# Receptor_Solo.net
KiCad netlist of a schematic drawn in EAGLE
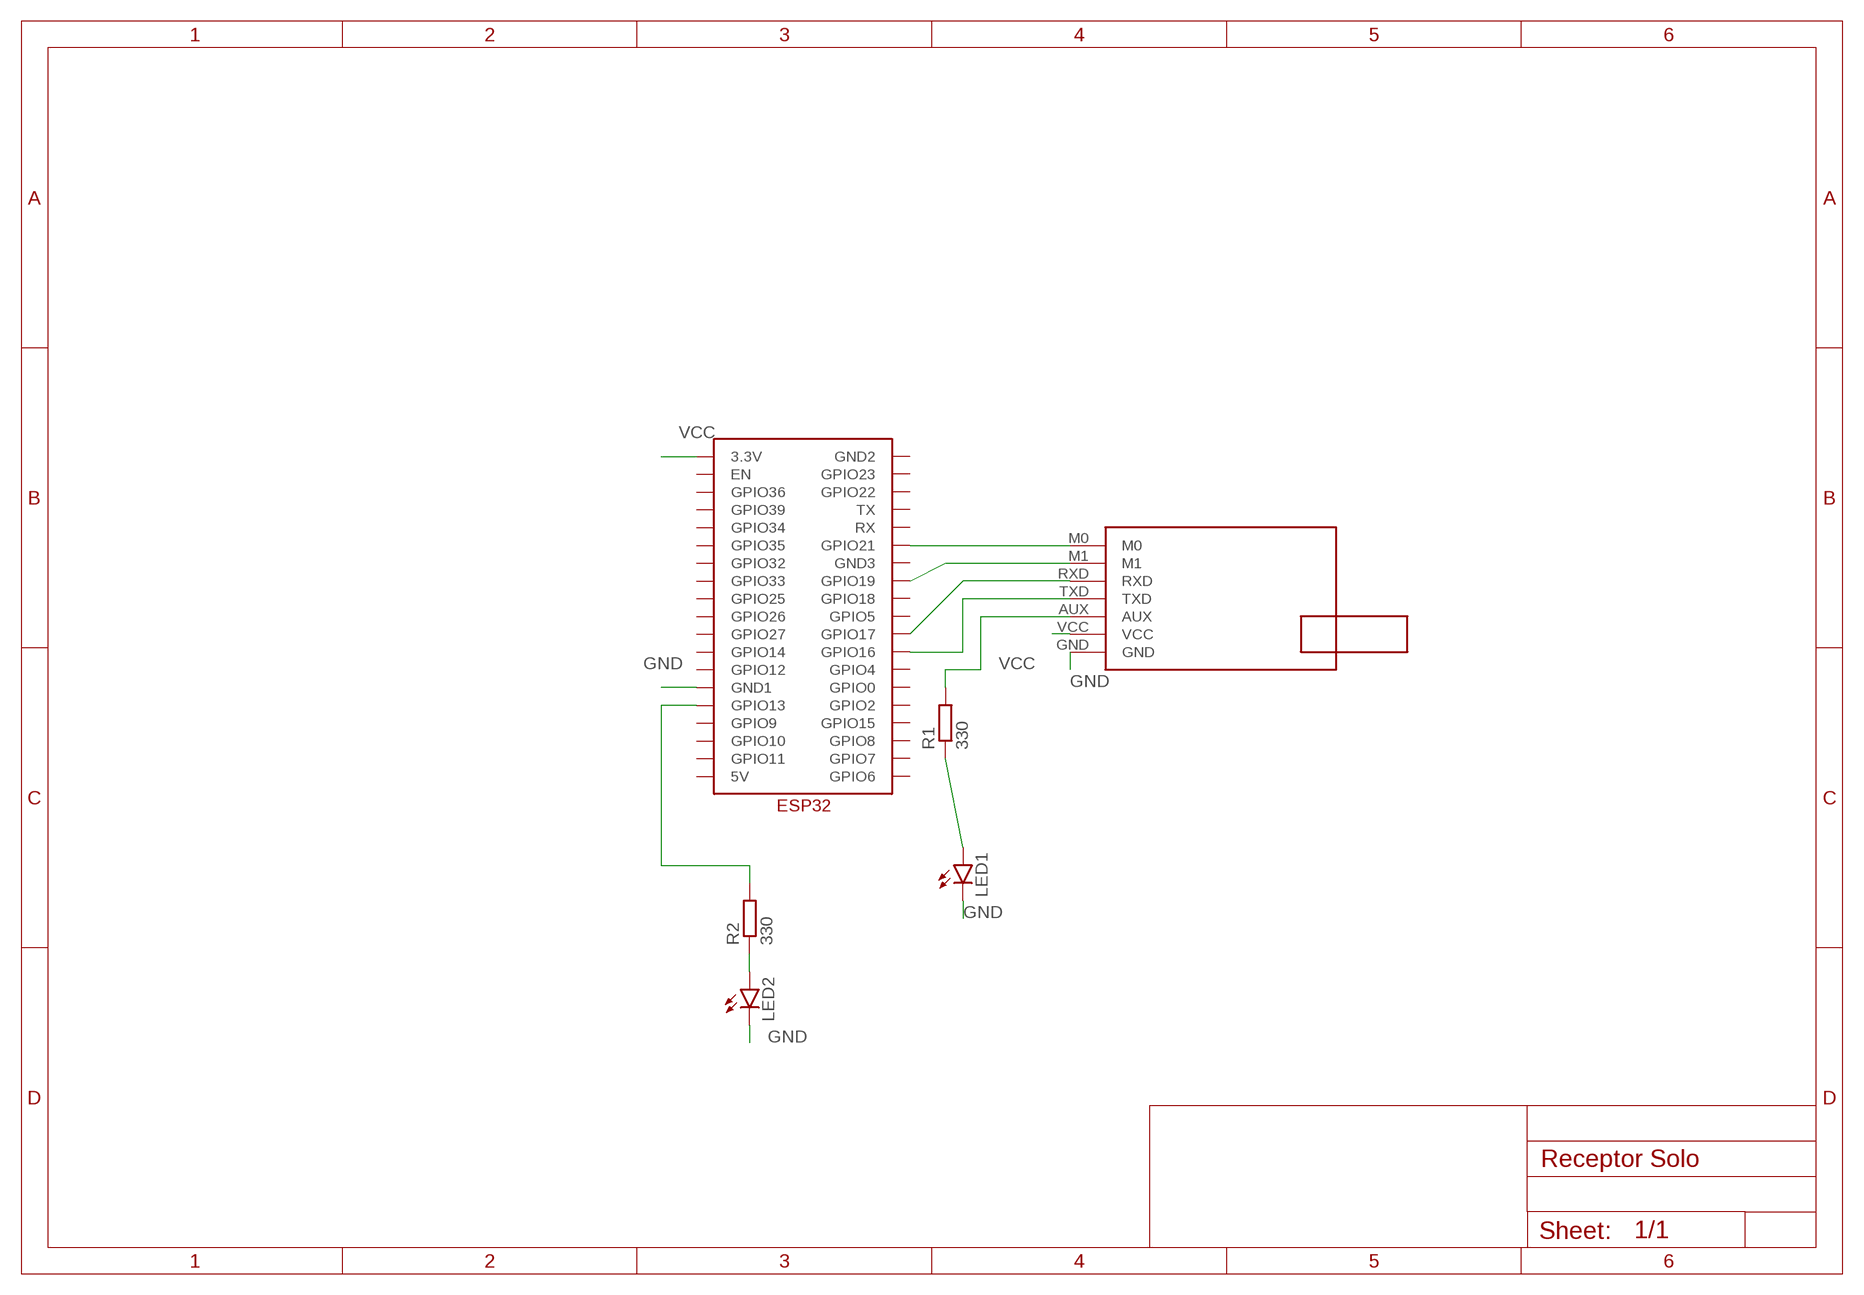
[diagram p0: schematic, sheet 1]

(export (version "E")
  (design (tool "Eeschema 10.0.6"))
  (components
    (comp (ref "LED1")
      (value "LED5MM")
      (footprint "eagle-import:LED5MM")
      (libsource (lib "eagle-import") (part "LED5MM"))
    )
    (comp (ref "LED2")
      (value "LED5MM")
      (footprint "eagle-import:LED5MM")
      (libsource (lib "eagle-import") (part "LED5MM"))
    )
    (comp (ref "R1")
      (value "330")
      (footprint "eagle-import:0207_10")
      (libsource (lib "eagle-import") (part "R-EU_0207/10"))
    )
    (comp (ref "R2")
      (value "330")
      (footprint "eagle-import:0207_10")
      (libsource (lib "eagle-import") (part "R-EU_0207/10"))
    )
    (comp (ref "U$1")
      (value "ESP32")
      (footprint "eagle-import:ESP32")
      (libsource (lib "eagle-import") (part "ESP32"))
    )
    (comp (ref "U$2")
      (value "E22-400T30D")
      (footprint "eagle-import:E22-400T30D_FOOTPRINT")
      (libsource (lib "eagle-import") (part "E22-400T30D"))
    )
  )
  (nets
    (net (code "1") (name "/GND") (class "Default")
      (node (ref "LED1") (pin "K") (pinfunction "C_K") (pintype "passive"))
      (node (ref "LED2") (pin "K") (pinfunction "C_K") (pintype "passive"))
      (node (ref "U$1") (pin "GND1") (pinfunction "GND1_GND1") (pintype "bidirectional"))
      (node (ref "U$2") (pin "GND") (pinfunction "GND_GND") (pintype "bidirectional"))
    )
    (net (code "2") (name "/VCC") (class "Default")
      (node (ref "U$1") (pin "3.3V") (pinfunction "3.3V_3.3V") (pintype "bidirectional"))
      (node (ref "U$2") (pin "VCC") (pinfunction "VCC_VCC") (pintype "bidirectional"))
    )
    (net (code "3") (name "Net-(LED1-PadA)") (class "Default")
      (node (ref "LED1") (pin "A") (pinfunction "A_A") (pintype "passive"))
      (node (ref "R1") (pin "1") (pinfunction "1_1") (pintype "passive"))
    )
    (net (code "4") (name "Net-(LED2-PadA)") (class "Default")
      (node (ref "LED2") (pin "A") (pinfunction "A_A") (pintype "passive"))
      (node (ref "R2") (pin "1") (pinfunction "1_1") (pintype "passive"))
    )
    (net (code "5") (name "Net-(R1-Pad2)") (class "Default")
      (node (ref "R1") (pin "2") (pinfunction "2_2") (pintype "passive"))
      (node (ref "U$2") (pin "AUX") (pinfunction "AUX_AUX") (pintype "bidirectional"))
    )
    (net (code "6") (name "Net-(R2-Pad2)") (class "Default")
      (node (ref "R2") (pin "2") (pinfunction "2_2") (pintype "passive"))
      (node (ref "U$1") (pin "GPIO13") (pinfunction "GPIO13_GPIO13") (pintype "bidirectional"))
    )
    (net (code "7") (name "Net-(U$1-PadGPIO16)") (class "Default")
      (node (ref "U$1") (pin "GPIO16") (pinfunction "GPIO16_GPIO16") (pintype "bidirectional"))
      (node (ref "U$2") (pin "TXD") (pinfunction "TXD_TXD") (pintype "bidirectional"))
    )
    (net (code "8") (name "Net-(U$1-PadGPIO17)") (class "Default")
      (node (ref "U$1") (pin "GPIO17") (pinfunction "GPIO17_GPIO17") (pintype "bidirectional"))
      (node (ref "U$2") (pin "RXD") (pinfunction "RXD_RXD") (pintype "bidirectional"))
    )
    (net (code "9") (name "Net-(U$1-PadGPIO19)") (class "Default")
      (node (ref "U$1") (pin "GPIO19") (pinfunction "GPIO19_GPIO19") (pintype "bidirectional"))
      (node (ref "U$2") (pin "M1") (pinfunction "M1_M1") (pintype "bidirectional"))
    )
    (net (code "10") (name "Net-(U$1-PadGPIO21)") (class "Default")
      (node (ref "U$1") (pin "GPIO21") (pinfunction "GPIO21_GPIO21") (pintype "bidirectional"))
      (node (ref "U$2") (pin "M0") (pinfunction "M0_M0") (pintype "bidirectional"))
    )
    (net (code "11") (name "unconnected-(U$1-Pad5V)") (class "Default")
      (node (ref "U$1") (pin "5V") (pinfunction "5V_5V") (pintype "bidirectional"))
    )
    (net (code "12") (name "unconnected-(U$1-PadEN)") (class "Default")
      (node (ref "U$1") (pin "EN") (pinfunction "EN_EN") (pintype "bidirectional"))
    )
    (net (code "13") (name "unconnected-(U$1-PadGND2)") (class "Default")
      (node (ref "U$1") (pin "GND2") (pinfunction "GND2_GND2") (pintype "bidirectional"))
    )
    (net (code "14") (name "unconnected-(U$1-PadGND3)") (class "Default")
      (node (ref "U$1") (pin "GND3") (pinfunction "GND3_GND3") (pintype "bidirectional"))
    )
    (net (code "15") (name "unconnected-(U$1-PadGPIO0)") (class "Default")
      (node (ref "U$1") (pin "GPIO0") (pinfunction "GPIO0_GPIO0") (pintype "bidirectional"))
    )
    (net (code "16") (name "unconnected-(U$1-PadGPIO2)") (class "Default")
      (node (ref "U$1") (pin "GPIO2") (pinfunction "GPIO2_GPIO2") (pintype "bidirectional"))
    )
    (net (code "17") (name "unconnected-(U$1-PadGPIO4)") (class "Default")
      (node (ref "U$1") (pin "GPIO4") (pinfunction "GPIO4_GPIO4") (pintype "bidirectional"))
    )
    (net (code "18") (name "unconnected-(U$1-PadGPIO5)") (class "Default")
      (node (ref "U$1") (pin "GPIO5") (pinfunction "GPIO5_GPIO5") (pintype "bidirectional"))
    )
    (net (code "19") (name "unconnected-(U$1-PadGPIO6)") (class "Default")
      (node (ref "U$1") (pin "GPIO6") (pinfunction "GPIO6_GPIO6") (pintype "bidirectional"))
    )
    (net (code "20") (name "unconnected-(U$1-PadGPIO7)") (class "Default")
      (node (ref "U$1") (pin "GPIO7") (pinfunction "GPIO7_GPIO7") (pintype "bidirectional"))
    )
    (net (code "21") (name "unconnected-(U$1-PadGPIO8)") (class "Default")
      (node (ref "U$1") (pin "GPIO8") (pinfunction "GPIO8_GPIO8") (pintype "bidirectional"))
    )
    (net (code "22") (name "unconnected-(U$1-PadGPIO9)") (class "Default")
      (node (ref "U$1") (pin "GPIO9") (pinfunction "GPIO9_GPIO9") (pintype "bidirectional"))
    )
    (net (code "23") (name "unconnected-(U$1-PadGPIO10)") (class "Default")
      (node (ref "U$1") (pin "GPIO10") (pinfunction "GPIO10_GPIO10") (pintype "bidirectional"))
    )
    (net (code "24") (name "unconnected-(U$1-PadGPIO11)") (class "Default")
      (node (ref "U$1") (pin "GPIO11") (pinfunction "GPIO11_GPIO11") (pintype "bidirectional"))
    )
    (net (code "25") (name "unconnected-(U$1-PadGPIO12)") (class "Default")
      (node (ref "U$1") (pin "GPIO12") (pinfunction "GPIO12_GPIO12") (pintype "bidirectional"))
    )
    (net (code "26") (name "unconnected-(U$1-PadGPIO14)") (class "Default")
      (node (ref "U$1") (pin "GPIO14") (pinfunction "GPIO14_GPIO14") (pintype "bidirectional"))
    )
    (net (code "27") (name "unconnected-(U$1-PadGPIO15)") (class "Default")
      (node (ref "U$1") (pin "GPIO15") (pinfunction "GPIO15_GPIO15") (pintype "bidirectional"))
    )
    (net (code "28") (name "unconnected-(U$1-PadGPIO18)") (class "Default")
      (node (ref "U$1") (pin "GPIO18") (pinfunction "GPIO18_GPIO18") (pintype "bidirectional"))
    )
    (net (code "29") (name "unconnected-(U$1-PadGPIO22)") (class "Default")
      (node (ref "U$1") (pin "GPIO22") (pinfunction "GPIO22_GPIO22") (pintype "bidirectional"))
    )
    (net (code "30") (name "unconnected-(U$1-PadGPIO23)") (class "Default")
      (node (ref "U$1") (pin "GPIO23") (pinfunction "GPIO23_GPIO23") (pintype "bidirectional"))
    )
    (net (code "31") (name "unconnected-(U$1-PadGPIO25)") (class "Default")
      (node (ref "U$1") (pin "GPIO25") (pinfunction "GPIO25_GPIO25") (pintype "bidirectional"))
    )
    (net (code "32") (name "unconnected-(U$1-PadGPIO26)") (class "Default")
      (node (ref "U$1") (pin "GPIO26") (pinfunction "GPIO26_GPIO26") (pintype "bidirectional"))
    )
    (net (code "33") (name "unconnected-(U$1-PadGPIO27)") (class "Default")
      (node (ref "U$1") (pin "GPIO27") (pinfunction "GPIO27_GPIO27") (pintype "bidirectional"))
    )
    (net (code "34") (name "unconnected-(U$1-PadGPIO32)") (class "Default")
      (node (ref "U$1") (pin "GPIO32") (pinfunction "GPIO32_GPIO32") (pintype "bidirectional"))
    )
    (net (code "35") (name "unconnected-(U$1-PadGPIO33)") (class "Default")
      (node (ref "U$1") (pin "GPIO33") (pinfunction "GPIO33_GPIO33") (pintype "bidirectional"))
    )
    (net (code "36") (name "unconnected-(U$1-PadGPIO34)") (class "Default")
      (node (ref "U$1") (pin "GPIO34") (pinfunction "GPIO34_GPIO34") (pintype "bidirectional"))
    )
    (net (code "37") (name "unconnected-(U$1-PadGPIO35)") (class "Default")
      (node (ref "U$1") (pin "GPIO35") (pinfunction "GPIO35_GPIO35") (pintype "bidirectional"))
    )
    (net (code "38") (name "unconnected-(U$1-PadGPIO36)") (class "Default")
      (node (ref "U$1") (pin "GPIO36") (pinfunction "GPIO36_GPIO36") (pintype "bidirectional"))
    )
    (net (code "39") (name "unconnected-(U$1-PadGPIO39)") (class "Default")
      (node (ref "U$1") (pin "GPIO39") (pinfunction "GPIO39_GPIO39") (pintype "bidirectional"))
    )
    (net (code "40") (name "unconnected-(U$1-PadRX)") (class "Default")
      (node (ref "U$1") (pin "RX") (pinfunction "RX_RX") (pintype "bidirectional"))
    )
    (net (code "41") (name "unconnected-(U$1-PadTX)") (class "Default")
      (node (ref "U$1") (pin "TX") (pinfunction "TX_TX") (pintype "bidirectional"))
    )
  )
)
